# PSU_LP5907_2V5.net
KiCad netlist of a schematic drawn in Altium Designer
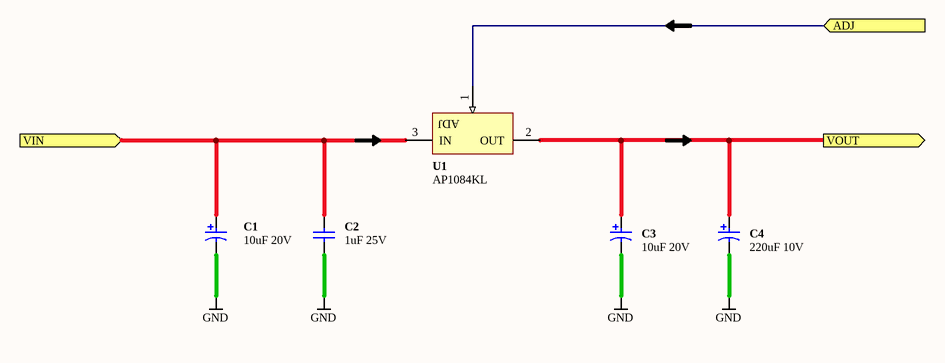
[diagram p0: PSU_LP5907_2V5.SchDoc]

(export (version "E")
  (design (tool "Eeschema 10.0.6"))
  (components
    (comp (ref "C1")
      (value "10uF 20V")
      (footprint "CAPC3528-STAR")
      (description "Capacitor, Tantalum, 10uF 10% 20V MCCT-B (3528)")
      (fields (field (name "TOLERANCE") "10 %"))
      (libsource (lib "altium-import") (part "root_0_CAP-P_"))
    )
    (comp (ref "C2")
      (value "1uF 25V")
      (footprint "CAPC3216-STAR")
      (description "Capacitor, Ceramic, 1uF 10% 25V 1206 (3216) X7R")
      (fields (field (name "TOLERANCE") "10 %"))
      (libsource (lib "altium-import") (part "root_0_CAP-NP_"))
    )
    (comp (ref "C3")
      (value "10uF 20V")
      (footprint "CAPC3528-STAR")
      (description "Capacitor, Tantalum, 10uF 10% 20V MCCT-B (3528)")
      (fields (field (name "TOLERANCE") "10 %"))
      (libsource (lib "altium-import") (part "root_0_CAP-P_"))
    )
    (comp (ref "C4")
      (value "220uF 10V")
      (footprint "CAPC7343-STAR")
      (description "Capacitor, Tantalum, 220uF 10% 10V MCCT-D (7343-31)")
      (fields (field (name "TOLERANCE") "10 %"))
      (libsource (lib "altium-import") (part "root_0_CAP-P_"))
    )
    (comp (ref "U1")
      (value "AP1084KL")
      (footprint "TO254P-3N")
      (description "AP1084KL, 5A Low Dropout Positive Adjustable Regulator")
      (libsource (lib "AltiumDesignLibrary") (part "AP1084KL"))
    )
  )
  (nets
    (net (code "1") (name "/ADJ") (class "Default")
      (node (ref "U1") (pin "1") (pinfunction "ADJ_1") (pintype "input"))
    )
    (net (code "2") (name "/VIN") (class "Default")
      (node (ref "C1") (pin "1") (pinfunction "1_1") (pintype "passive"))
      (node (ref "C2") (pin "1") (pinfunction "1_1") (pintype "passive"))
      (node (ref "U1") (pin "3") (pinfunction "IN_3") (pintype "power_in"))
    )
    (net (code "3") (name "/VOUT") (class "Default")
      (node (ref "C3") (pin "1") (pinfunction "1_1") (pintype "passive"))
      (node (ref "C4") (pin "1") (pinfunction "1_1") (pintype "passive"))
      (node (ref "U1") (pin "2") (pinfunction "OUT_2") (pintype "power_in"))
    )
    (net (code "4") (name "GND") (class "Default")
      (node (ref "C1") (pin "2") (pinfunction "2_2") (pintype "passive"))
      (node (ref "C2") (pin "2") (pinfunction "2_2") (pintype "passive"))
      (node (ref "C3") (pin "2") (pinfunction "2_2") (pintype "passive"))
      (node (ref "C4") (pin "2") (pinfunction "2_2") (pintype "passive"))
    )
  )
)
